# NG2092_USB.net
KiCad netlist of a schematic drawn in Altium Designer
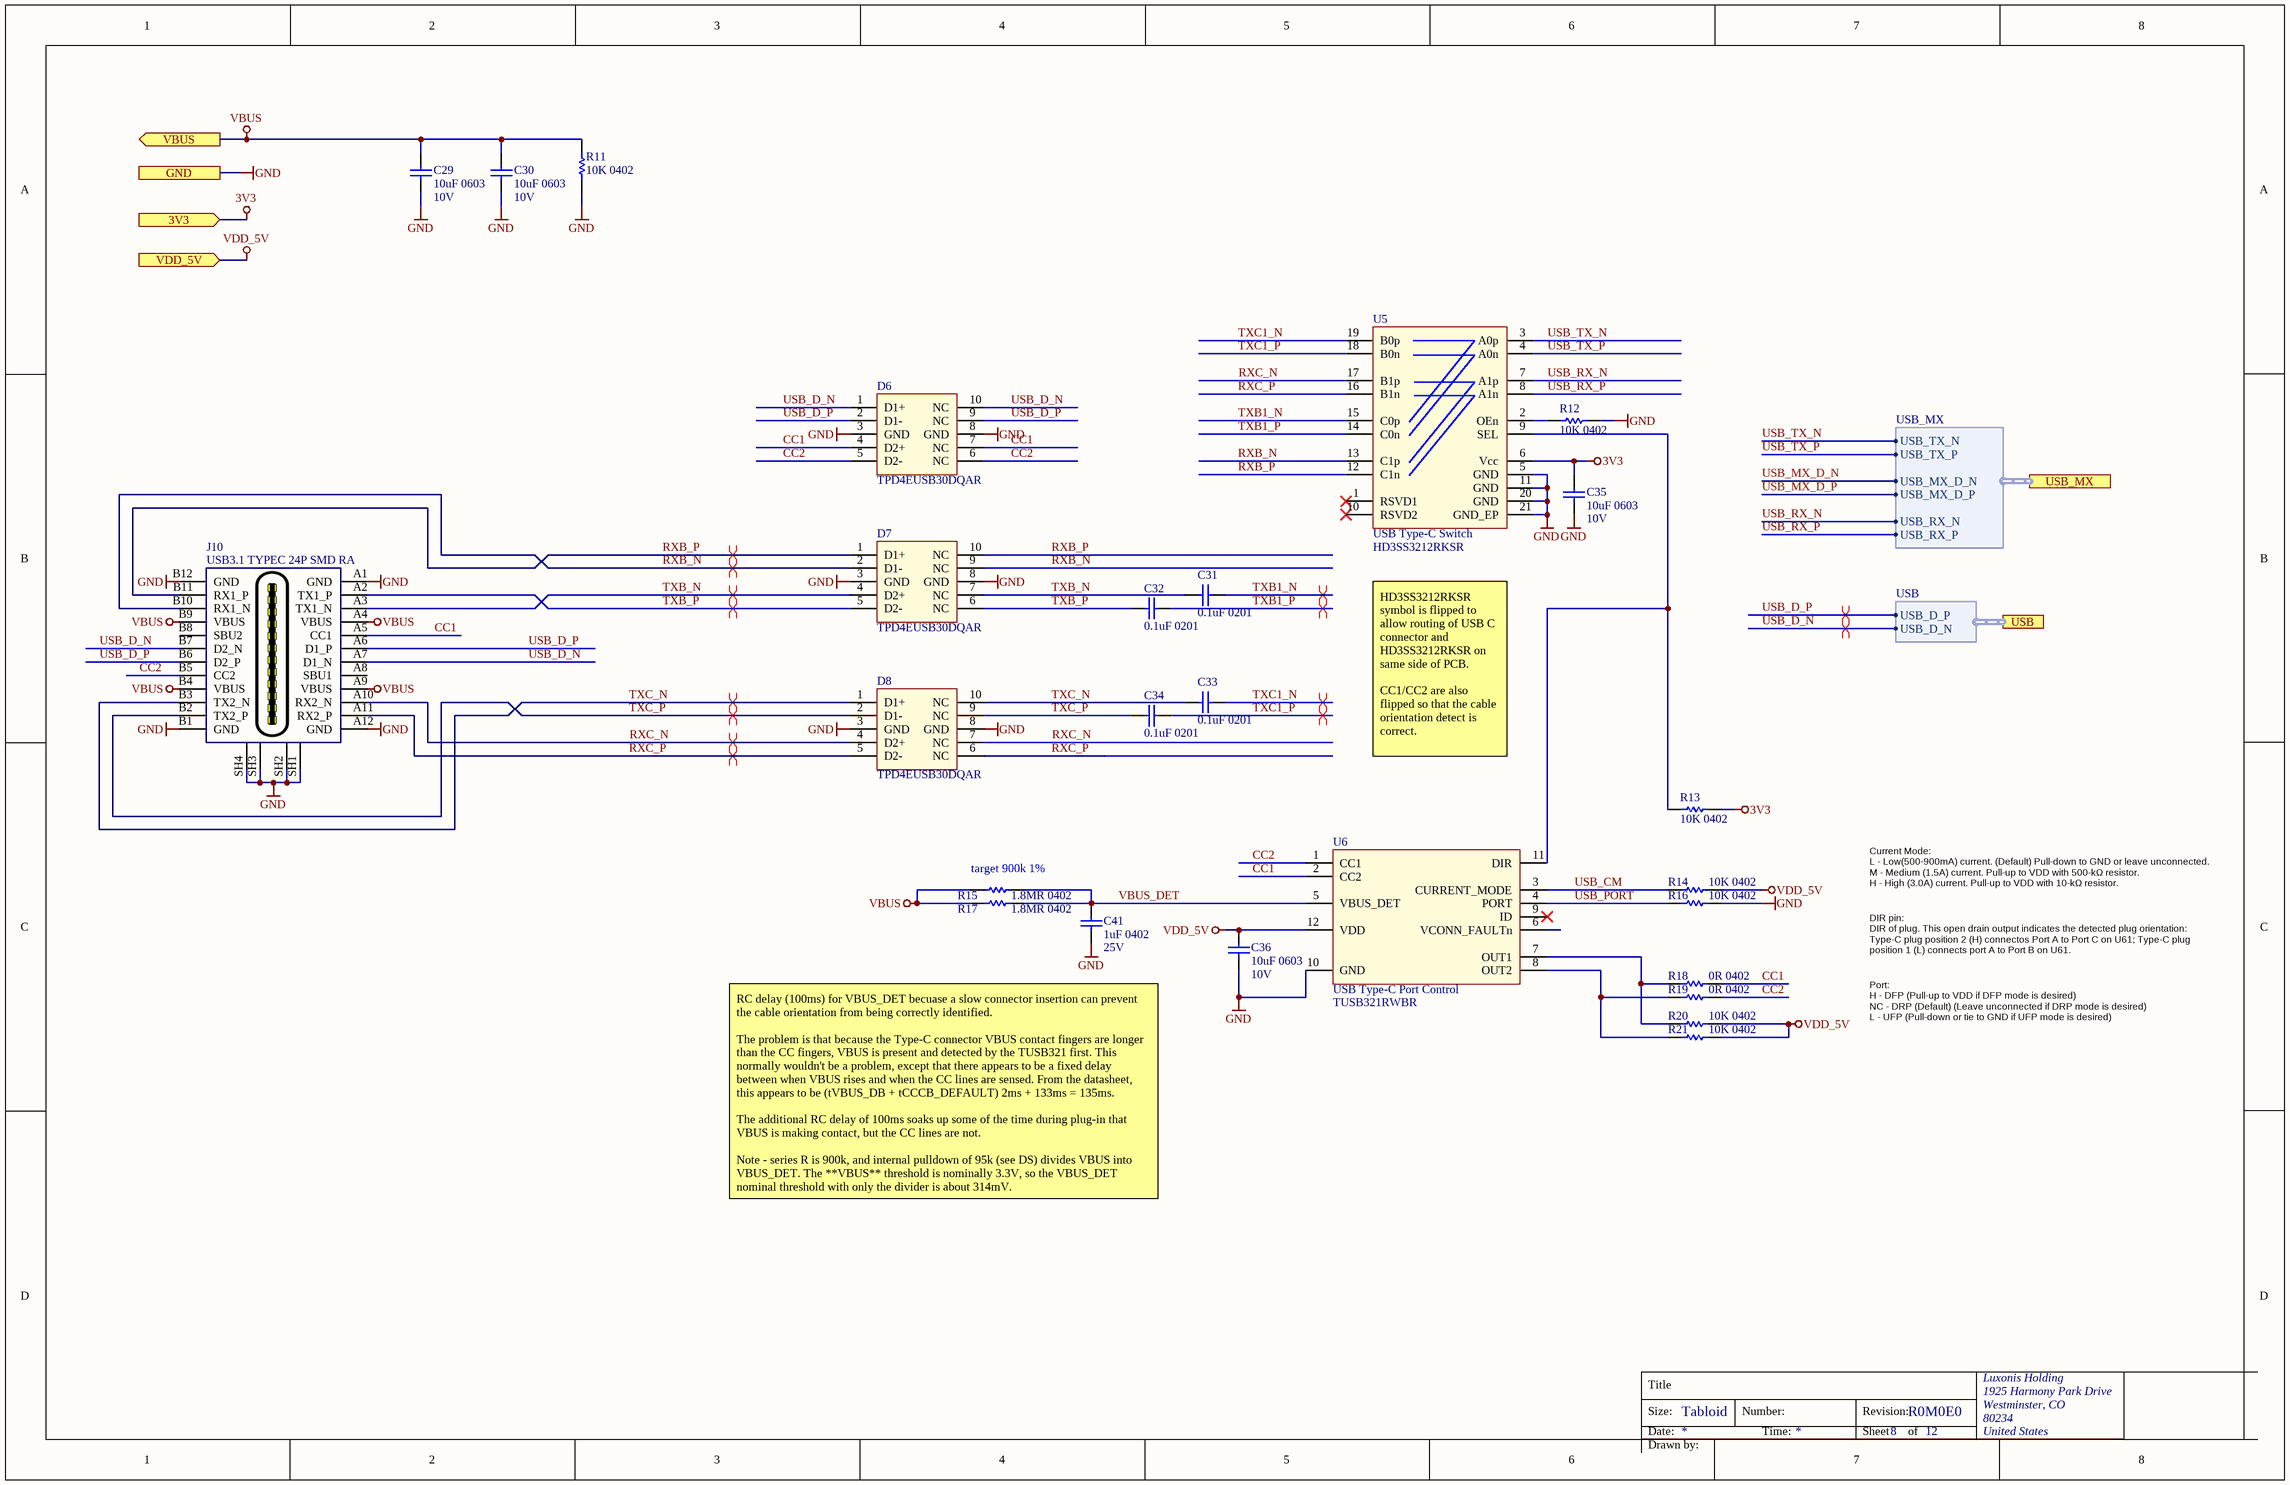
[diagram p0: NG2092_USB.SchDoc]

(export (version "E")
  (design (tool "Eeschema 10.0.6"))
  (components
    (comp (ref "C29")
      (value "10uF 0603")
      (footprint "CAP_Altium_Vault_Generic:CAPC0603(1608)100_L")
      (description "CAP CER 10UF 10V X5R 0603 20%")
      (fields (field (name "TOLERANCE") "20%") (field (name "VOLTAGE RATING") "10V"))
      (libsource (lib "LuxonisMaster") (part "GRM188R61A106ME69D"))
    )
    (comp (ref "C30")
      (value "10uF 0603")
      (footprint "CAP_Altium_Vault_Generic:CAPC0603(1608)100_L")
      (description "CAP CER 10UF 10V X5R 0603 20%")
      (fields (field (name "TOLERANCE") "20%") (field (name "VOLTAGE RATING") "10V"))
      (libsource (lib "LuxonisMaster") (part "GRM188R61A106ME69D"))
    )
    (comp (ref "C31")
      (value "0.1uF 0201")
      (footprint "CAP_Altium_Vault_Generic:CAPC0201(0603)33_L")
      (description "CAP CER 0.1UF 10V X5R 0201")
      (fields (field (name "TOLERANCE") "10%") (field (name "VOLTAGE") "10V"))
      (libsource (lib "LuxonisMaster") (part "GRM033R61A104KE15D"))
    )
    (comp (ref "C32")
      (value "0.1uF 0201")
      (footprint "CAP_Altium_Vault_Generic:CAPC0201(0603)33_L")
      (description "CAP CER 0.1UF 10V X5R 0201")
      (fields (field (name "TOLERANCE") "10%") (field (name "VOLTAGE") "10V"))
      (libsource (lib "LuxonisMaster") (part "GRM033R61A104KE15D"))
    )
    (comp (ref "C33")
      (value "0.1uF 0201")
      (footprint "CAP_Altium_Vault_Generic:CAPC0201(0603)33_L")
      (description "CAP CER 0.1UF 10V X5R 0201")
      (fields (field (name "TOLERANCE") "10%") (field (name "VOLTAGE") "10V"))
      (libsource (lib "LuxonisMaster") (part "GRM033R61A104KE15D"))
    )
    (comp (ref "C34")
      (value "0.1uF 0201")
      (footprint "CAP_Altium_Vault_Generic:CAPC0201(0603)33_L")
      (description "CAP CER 0.1UF 10V X5R 0201")
      (fields (field (name "TOLERANCE") "10%") (field (name "VOLTAGE") "10V"))
      (libsource (lib "LuxonisMaster") (part "GRM033R61A104KE15D"))
    )
    (comp (ref "C35")
      (value "10uF 0603")
      (footprint "CAP_Altium_Vault_Generic:CAPC0603(1608)100_L")
      (description "CAP CER 10UF 10V X5R 0603 20%")
      (fields (field (name "TOLERANCE") "20%") (field (name "VOLTAGE RATING") "10V"))
      (libsource (lib "LuxonisMaster") (part "GRM188R61A106ME69D"))
    )
    (comp (ref "C36")
      (value "10uF 0603")
      (footprint "CAP_Altium_Vault_Generic:CAPC0603(1608)100_L")
      (description "CAP CER 10UF 10V X5R 0603 20%")
      (fields (field (name "TOLERANCE") "20%") (field (name "VOLTAGE RATING") "10V"))
      (libsource (lib "LuxonisMaster") (part "GRM188R61A106ME69D"))
    )
    (comp (ref "C41")
      (value "1uF 0402")
      (footprint "CAP_Altium_Vault_Generic:CAPC0402(1005)70_N")
      (description "CAP CER 1UF 25V X5R 0402 10%")
      (fields
        (field (name "TOLERANCE") "10%")
        (field (name "VOLTAGE") "25V")
        (field (name "VOLTAGE RATING") "25V")
      )
      (libsource (lib "LuxonisMaster") (part "GRM155R61E105KA12D"))
    )
    (comp (ref "D6")
      (value "TPD4EUSB30DQAR")
      (footprint "LuxonisMaster:TPD4EUSB30DQAR")
      (description "TVS DIODE 5.5V 8V 10SON 8V Clamp 1A (8/20µs) Ipp Tvs Diode Surface Mount 10-USON (2.5x1)")
      (libsource (lib "LuxonisMaster") (part "TPD4EUSB30DQAR"))
    )
    (comp (ref "D7")
      (value "TPD4EUSB30DQAR")
      (footprint "LuxonisMaster:TPD4EUSB30DQAR")
      (description "TVS DIODE 5.5V 8V 10SON 8V Clamp 1A (8/20µs) Ipp Tvs Diode Surface Mount 10-USON (2.5x1)")
      (libsource (lib "LuxonisMaster") (part "TPD4EUSB30DQAR"))
    )
    (comp (ref "D8")
      (value "TPD4EUSB30DQAR")
      (footprint "LuxonisMaster:TPD4EUSB30DQAR")
      (description "TVS DIODE 5.5V 8V 10SON 8V Clamp 1A (8/20µs) Ipp Tvs Diode Surface Mount 10-USON (2.5x1)")
      (libsource (lib "LuxonisMaster") (part "TPD4EUSB30DQAR"))
    )
    (comp (ref "J10")
      (value "USB3.1 TYPEC 24P SMD RA")
      (footprint "LuxonisMaster:105450-0101")
      (description "CONN RCP USB3.1 TYPEC 24P SMD RA")
      (libsource (lib "LuxonisMaster") (part "105450-0101"))
    )
    (comp (ref "R11")
      (value "10K 0402")
      (footprint "RES_Altium_Vault_Generic:RESC0402(1005)_L")
      (fields (field (name "TOLERANCE") "1%"))
      (libsource (lib "LuxonisMaster") (part "RC0402FR-1310KL"))
    )
    (comp (ref "R12")
      (value "10K 0402")
      (footprint "RES_Altium_Vault_Generic:RESC0402(1005)_L")
      (fields (field (name "TOLERANCE") "1%"))
      (libsource (lib "LuxonisMaster") (part "RC0402FR-1310KL"))
    )
    (comp (ref "R13")
      (value "10K 0402")
      (footprint "RES_Altium_Vault_Generic:RESC0402(1005)_L")
      (fields (field (name "TOLERANCE") "1%"))
      (libsource (lib "LuxonisMaster") (part "RC0402FR-1310KL"))
    )
    (comp (ref "R14")
      (value "10K 0402")
      (footprint "RES_Altium_Vault_Generic:RESC0402(1005)_L")
      (fields (field (name "TOLERANCE") "1%"))
      (libsource (lib "LuxonisMaster") (part "RC0402FR-1310KL"))
    )
    (comp (ref "R15")
      (value "1.8MR 0402")
      (footprint "RES_Altium_Vault_Generic:RESC0402(1005)_L")
      (description "RES SMD 1.8M OHM 1% 1/16W 0402")
      (fields (field (name "TOLERANCE") "1%"))
      (libsource (lib "LuxonisMaster") (part "CRCW04021M80FKED"))
    )
    (comp (ref "R16")
      (value "10K 0402")
      (footprint "RES_Altium_Vault_Generic:RESC0402(1005)_L")
      (fields (field (name "TOLERANCE") "1%"))
      (libsource (lib "LuxonisMaster") (part "RC0402FR-1310KL"))
    )
    (comp (ref "R17")
      (value "1.8MR 0402")
      (footprint "RES_Altium_Vault_Generic:RESC0402(1005)_L")
      (description "RES SMD 1.8M OHM 1% 1/16W 0402")
      (fields (field (name "TOLERANCE") "1%"))
      (libsource (lib "LuxonisMaster") (part "CRCW04021M80FKED"))
    )
    (comp (ref "R18")
      (value "0R 0402")
      (footprint "RES_Altium_Vault_Generic:RESC0402(1005)_L")
      (description "RES SMD 0 OHM JUMPER 1/16W 0402")
      (fields (field (name "TOLERANCE") "5%"))
      (libsource (lib "LuxonisMaster") (part "CRCW04020000Z0ED"))
    )
    (comp (ref "R19")
      (value "0R 0402")
      (footprint "RES_Altium_Vault_Generic:RESC0402(1005)_L")
      (description "RES SMD 0 OHM JUMPER 1/16W 0402")
      (fields (field (name "TOLERANCE") "5%"))
      (libsource (lib "LuxonisMaster") (part "CRCW04020000Z0ED"))
    )
    (comp (ref "R20")
      (value "10K 0402")
      (footprint "RES_Altium_Vault_Generic:RESC0402(1005)_L")
      (fields (field (name "TOLERANCE") "1%"))
      (libsource (lib "LuxonisMaster") (part "RC0402FR-1310KL"))
    )
    (comp (ref "R21")
      (value "10K 0402")
      (footprint "RES_Altium_Vault_Generic:RESC0402(1005)_L")
      (fields (field (name "TOLERANCE") "1%"))
      (libsource (lib "LuxonisMaster") (part "RC0402FR-1310KL"))
    )
    (comp (ref "U5")
      (value "USB Type-C Switch")
      (footprint "LuxonisMaster:HD3SS3212RKSR")
      (description "IC MUX 2:1 8 OHM 20VQFN")
      (fields (field (name "MANUFACTURER PART NUMBER 1") "HD3SS3212RKSR"))
      (libsource (lib "LuxonisMaster") (part "HD3SS3212RKSR"))
    )
    (comp (ref "U6")
      (value "USB Type-C Port Control")
      (footprint "LuxonisMaster:TUSB321RWBR")
      (description "IC USB PORT CONTROL TYPE-C 12X2Q")
      (fields (field (name "MANUFACTURER PART NUMBER 1") "TUSB321RWBR"))
      (libsource (lib "LuxonisMaster") (part "TUSB321RWBR"))
    )
  )
  (nets
    (net (code "3") (name "/CC1") (class "Default")
      (node (ref "D6") (pin "4") (pinfunction "D2+_4") (pintype "passive"))
      (node (ref "D6") (pin "7") (pinfunction "NC_7") (pintype "passive"))
      (node (ref "J10") (pin "A5") (pinfunction "CC1_A5") (pintype "passive"))
      (node (ref "R18") (pin "2") (pinfunction "2_2") (pintype "passive"))
      (node (ref "U6") (pin "2") (pinfunction "CC2_2") (pintype "passive"))
    )
    (net (code "4") (name "/CC2") (class "Default")
      (node (ref "D6") (pin "5") (pinfunction "D2-_5") (pintype "passive"))
      (node (ref "D6") (pin "6") (pinfunction "NC_6") (pintype "passive"))
      (node (ref "J10") (pin "B5") (pinfunction "CC2_B5") (pintype "passive"))
      (node (ref "R19") (pin "2") (pinfunction "2_2") (pintype "passive"))
      (node (ref "U6") (pin "1") (pinfunction "CC1_1") (pintype "passive"))
    )
    (net (code "5") (name "/RXB_N") (class "Default")
      (node (ref "D7") (pin "2") (pinfunction "D1-_2") (pintype "passive"))
      (node (ref "D7") (pin "9") (pinfunction "NC_9") (pintype "passive"))
      (node (ref "J10") (pin "B10") (pinfunction "RX1_N_B10") (pintype "passive"))
      (node (ref "U5") (pin "13") (pinfunction "C1p_13") (pintype "passive"))
    )
    (net (code "6") (name "/RXB_P") (class "Default")
      (node (ref "D7") (pin "1") (pinfunction "D1+_1") (pintype "passive"))
      (node (ref "D7") (pin "10") (pinfunction "NC_10") (pintype "passive"))
      (node (ref "J10") (pin "B11") (pinfunction "RX1_P_B11") (pintype "passive"))
      (node (ref "U5") (pin "12") (pinfunction "C1n_12") (pintype "passive"))
    )
    (net (code "7") (name "/RXC_N") (class "Default")
      (node (ref "D8") (pin "4") (pinfunction "D2+_4") (pintype "passive"))
      (node (ref "D8") (pin "7") (pinfunction "NC_7") (pintype "passive"))
      (node (ref "J10") (pin "A10") (pinfunction "RX2_N_A10") (pintype "passive"))
      (node (ref "U5") (pin "17") (pinfunction "B1p_17") (pintype "passive"))
    )
    (net (code "8") (name "/RXC_P") (class "Default")
      (node (ref "D8") (pin "5") (pinfunction "D2-_5") (pintype "passive"))
      (node (ref "D8") (pin "6") (pinfunction "NC_6") (pintype "passive"))
      (node (ref "J10") (pin "A11") (pinfunction "RX2_P_A11") (pintype "passive"))
      (node (ref "U5") (pin "16") (pinfunction "B1n_16") (pintype "passive"))
    )
    (net (code "9") (name "/TXB1_N") (class "Default")
      (node (ref "C31") (pin "2") (pinfunction "2_2") (pintype "passive"))
      (node (ref "U5") (pin "15") (pinfunction "C0p_15") (pintype "passive"))
    )
    (net (code "10") (name "/TXB1_P") (class "Default")
      (node (ref "C32") (pin "2") (pinfunction "2_2") (pintype "passive"))
      (node (ref "U5") (pin "14") (pinfunction "C0n_14") (pintype "passive"))
    )
    (net (code "11") (name "/TXB_N") (class "Default")
      (node (ref "C31") (pin "1") (pinfunction "1_1") (pintype "passive"))
      (node (ref "D7") (pin "4") (pinfunction "D2+_4") (pintype "passive"))
      (node (ref "D7") (pin "7") (pinfunction "NC_7") (pintype "passive"))
      (node (ref "J10") (pin "A3") (pinfunction "TX1_N_A3") (pintype "passive"))
    )
    (net (code "12") (name "/TXB_P") (class "Default")
      (node (ref "C32") (pin "1") (pinfunction "1_1") (pintype "passive"))
      (node (ref "D7") (pin "5") (pinfunction "D2-_5") (pintype "passive"))
      (node (ref "D7") (pin "6") (pinfunction "NC_6") (pintype "passive"))
      (node (ref "J10") (pin "A2") (pinfunction "TX1_P_A2") (pintype "passive"))
    )
    (net (code "13") (name "/TXC1_N") (class "Default")
      (node (ref "C33") (pin "2") (pinfunction "2_2") (pintype "passive"))
      (node (ref "U5") (pin "19") (pinfunction "B0p_19") (pintype "passive"))
    )
    (net (code "14") (name "/TXC1_P") (class "Default")
      (node (ref "C34") (pin "2") (pinfunction "2_2") (pintype "passive"))
      (node (ref "U5") (pin "18") (pinfunction "B0n_18") (pintype "passive"))
    )
    (net (code "15") (name "/TXC_N") (class "Default")
      (node (ref "C33") (pin "1") (pinfunction "1_1") (pintype "passive"))
      (node (ref "D8") (pin "1") (pinfunction "D1+_1") (pintype "passive"))
      (node (ref "D8") (pin "10") (pinfunction "NC_10") (pintype "passive"))
      (node (ref "J10") (pin "B3") (pinfunction "TX2_N_B3") (pintype "passive"))
    )
    (net (code "16") (name "/TXC_P") (class "Default")
      (node (ref "C34") (pin "1") (pinfunction "1_1") (pintype "passive"))
      (node (ref "D8") (pin "2") (pinfunction "D1-_2") (pintype "passive"))
      (node (ref "D8") (pin "9") (pinfunction "NC_9") (pintype "passive"))
      (node (ref "J10") (pin "B2") (pinfunction "TX2_P_B2") (pintype "passive"))
    )
    (net (code "17") (name "/USB_CM") (class "Default")
      (node (ref "R14") (pin "1") (pinfunction "1_1") (pintype "passive"))
      (node (ref "U6") (pin "3") (pinfunction "CURRENT_MODE_3") (pintype "passive"))
    )
    (net (code "18") (name "/USB_D_N") (class "Default")
      (node (ref "D6") (pin "1") (pinfunction "D1+_1") (pintype "passive"))
      (node (ref "D6") (pin "10") (pinfunction "NC_10") (pintype "passive"))
      (node (ref "J10") (pin "A7") (pinfunction "D1_N_A7") (pintype "passive"))
      (node (ref "J10") (pin "B7") (pinfunction "D2_N_B7") (pintype "passive"))
    )
    (net (code "19") (name "/USB_D_P") (class "Default")
      (node (ref "D6") (pin "2") (pinfunction "D1-_2") (pintype "passive"))
      (node (ref "D6") (pin "9") (pinfunction "NC_9") (pintype "passive"))
      (node (ref "J10") (pin "A6") (pinfunction "D1_P_A6") (pintype "passive"))
      (node (ref "J10") (pin "B6") (pinfunction "D2_P_B6") (pintype "passive"))
    )
    (net (code "22") (name "/USB_PORT") (class "Default")
      (node (ref "R16") (pin "1") (pinfunction "1_1") (pintype "passive"))
      (node (ref "U6") (pin "4") (pinfunction "PORT_4") (pintype "passive"))
    )
    (net (code "23") (name "/USB_RX_N") (class "Default")
      (node (ref "U5") (pin "7") (pinfunction "A1p_7") (pintype "passive"))
    )
    (net (code "24") (name "/USB_RX_P") (class "Default")
      (node (ref "U5") (pin "8") (pinfunction "A1n_8") (pintype "passive"))
    )
    (net (code "25") (name "/USB_TX_N") (class "Default")
      (node (ref "U5") (pin "3") (pinfunction "A0p_3") (pintype "passive"))
    )
    (net (code "26") (name "/USB_TX_P") (class "Default")
      (node (ref "U5") (pin "4") (pinfunction "A0n_4") (pintype "passive"))
    )
    (net (code "27") (name "/VBUS_DET") (class "Default")
      (node (ref "C41") (pin "2") (pinfunction "2_2") (pintype "passive"))
      (node (ref "R15") (pin "2") (pinfunction "2_2") (pintype "passive"))
      (node (ref "R17") (pin "2") (pinfunction "2_2") (pintype "passive"))
      (node (ref "U6") (pin "5") (pinfunction "VBUS_DET_5") (pintype "passive"))
    )
    (net (code "30") (name "3V3") (class "Default")
      (node (ref "C35") (pin "2") (pinfunction "2_2") (pintype "passive"))
      (node (ref "R13") (pin "2") (pinfunction "2_2") (pintype "passive"))
      (node (ref "U5") (pin "6") (pinfunction "Vcc_6") (pintype "passive"))
    )
    (net (code "31") (name "GND") (class "Default")
      (node (ref "C29") (pin "1") (pinfunction "1_1") (pintype "passive"))
      (node (ref "C30") (pin "1") (pinfunction "1_1") (pintype "passive"))
      (node (ref "C35") (pin "1") (pinfunction "1_1") (pintype "passive"))
      (node (ref "C36") (pin "1") (pinfunction "1_1") (pintype "passive"))
      (node (ref "C41") (pin "1") (pinfunction "1_1") (pintype "passive"))
      (node (ref "D6") (pin "3") (pinfunction "GND_3") (pintype "passive"))
      (node (ref "D6") (pin "8") (pinfunction "GND_8") (pintype "passive"))
      (node (ref "D7") (pin "3") (pinfunction "GND_3") (pintype "passive"))
      (node (ref "D7") (pin "8") (pinfunction "GND_8") (pintype "passive"))
      (node (ref "D8") (pin "3") (pinfunction "GND_3") (pintype "passive"))
      (node (ref "D8") (pin "8") (pinfunction "GND_8") (pintype "passive"))
      (node (ref "J10") (pin "A1") (pinfunction "GND_A1") (pintype "passive"))
      (node (ref "J10") (pin "A12") (pinfunction "GND_A12") (pintype "passive"))
      (node (ref "J10") (pin "B1") (pinfunction "GND_B1") (pintype "passive"))
      (node (ref "J10") (pin "B12") (pinfunction "GND_B12") (pintype "passive"))
      (node (ref "J10") (pin "SH1") (pinfunction "SH_SH1") (pintype "passive"))
      (node (ref "J10") (pin "SH2") (pinfunction "SH_SH2") (pintype "passive"))
      (node (ref "J10") (pin "SH3") (pinfunction "SH_SH3") (pintype "passive"))
      (node (ref "J10") (pin "SH4") (pinfunction "SH_SH4") (pintype "passive"))
      (node (ref "R11") (pin "1") (pinfunction "1_1") (pintype "passive"))
      (node (ref "R12") (pin "2") (pinfunction "2_2") (pintype "passive"))
      (node (ref "R16") (pin "2") (pinfunction "2_2") (pintype "passive"))
      (node (ref "U5") (pin "11") (pinfunction "GND_11") (pintype "passive"))
      (node (ref "U5") (pin "20") (pinfunction "GND_20") (pintype "passive"))
      (node (ref "U5") (pin "21") (pinfunction "GND_EP_21") (pintype "passive"))
      (node (ref "U5") (pin "5") (pinfunction "GND_5") (pintype "passive"))
      (node (ref "U6") (pin "10") (pinfunction "GND_10") (pintype "passive"))
    )
    (net (code "32") (name "Net-(U5-OEn)") (class "Default")
      (node (ref "R12") (pin "1") (pinfunction "1_1") (pintype "passive"))
      (node (ref "U5") (pin "2") (pinfunction "OEn_2") (pintype "passive"))
    )
    (net (code "33") (name "Net-(U5-SEL)") (class "Default")
      (node (ref "R13") (pin "1") (pinfunction "1_1") (pintype "passive"))
      (node (ref "U5") (pin "9") (pinfunction "SEL_9") (pintype "passive"))
      (node (ref "U6") (pin "11") (pinfunction "DIR_11") (pintype "passive"))
    )
    (net (code "34") (name "Net-(U6-OUT1)") (class "Default")
      (node (ref "R18") (pin "1") (pinfunction "1_1") (pintype "passive"))
      (node (ref "R20") (pin "1") (pinfunction "1_1") (pintype "passive"))
      (node (ref "U6") (pin "7") (pinfunction "OUT1_7") (pintype "passive"))
    )
    (net (code "35") (name "Net-(U6-OUT2)") (class "Default")
      (node (ref "R19") (pin "1") (pinfunction "1_1") (pintype "passive"))
      (node (ref "R21") (pin "1") (pinfunction "1_1") (pintype "passive"))
      (node (ref "U6") (pin "8") (pinfunction "OUT2_8") (pintype "passive"))
    )
    (net (code "36") (name "VBUS") (class "Default")
      (node (ref "C29") (pin "2") (pinfunction "2_2") (pintype "passive"))
      (node (ref "C30") (pin "2") (pinfunction "2_2") (pintype "passive"))
      (node (ref "J10") (pin "A4") (pinfunction "VBUS_A4") (pintype "passive"))
      (node (ref "J10") (pin "A9") (pinfunction "VBUS_A9") (pintype "passive"))
      (node (ref "J10") (pin "B4") (pinfunction "VBUS_B4") (pintype "passive"))
      (node (ref "J10") (pin "B9") (pinfunction "VBUS_B9") (pintype "passive"))
      (node (ref "R11") (pin "2") (pinfunction "2_2") (pintype "passive"))
      (node (ref "R15") (pin "1") (pinfunction "1_1") (pintype "passive"))
      (node (ref "R17") (pin "1") (pinfunction "1_1") (pintype "passive"))
    )
    (net (code "37") (name "VDD_5V") (class "Default")
      (node (ref "C36") (pin "2") (pinfunction "2_2") (pintype "passive"))
      (node (ref "R14") (pin "2") (pinfunction "2_2") (pintype "passive"))
      (node (ref "R20") (pin "2") (pinfunction "2_2") (pintype "passive"))
      (node (ref "R21") (pin "2") (pinfunction "2_2") (pintype "passive"))
      (node (ref "U6") (pin "12") (pinfunction "VDD_12") (pintype "passive"))
    )
    (net (code "38") (name "unconnected-(J10-SBU1-PadA8)") (class "Default")
      (node (ref "J10") (pin "A8") (pinfunction "SBU1_A8") (pintype "passive"))
    )
    (net (code "39") (name "unconnected-(J10-SBU2-PadB8)") (class "Default")
      (node (ref "J10") (pin "B8") (pinfunction "SBU2_B8") (pintype "passive"))
    )
    (net (code "40") (name "unconnected-(U5-RSVD1-Pad1)") (class "Default")
      (node (ref "U5") (pin "1") (pinfunction "RSVD1_1") (pintype "passive+no_connect"))
    )
    (net (code "41") (name "unconnected-(U5-RSVD2-Pad10)") (class "Default")
      (node (ref "U5") (pin "10") (pinfunction "RSVD2_10") (pintype "passive+no_connect"))
    )
    (net (code "42") (name "unconnected-(U6-ID-Pad9)") (class "Default")
      (node (ref "U6") (pin "9") (pinfunction "ID_9") (pintype "passive+no_connect"))
    )
    (net (code "43") (name "unconnected-(U6-VCONN_FAULTn-Pad6)") (class "Default")
      (node (ref "U6") (pin "6") (pinfunction "VCONN_FAULTn_6") (pintype "passive"))
    )
  )
)
